# wlpkt1_cpu.net
KiCad netlist of a schematic drawn in Altium Designer
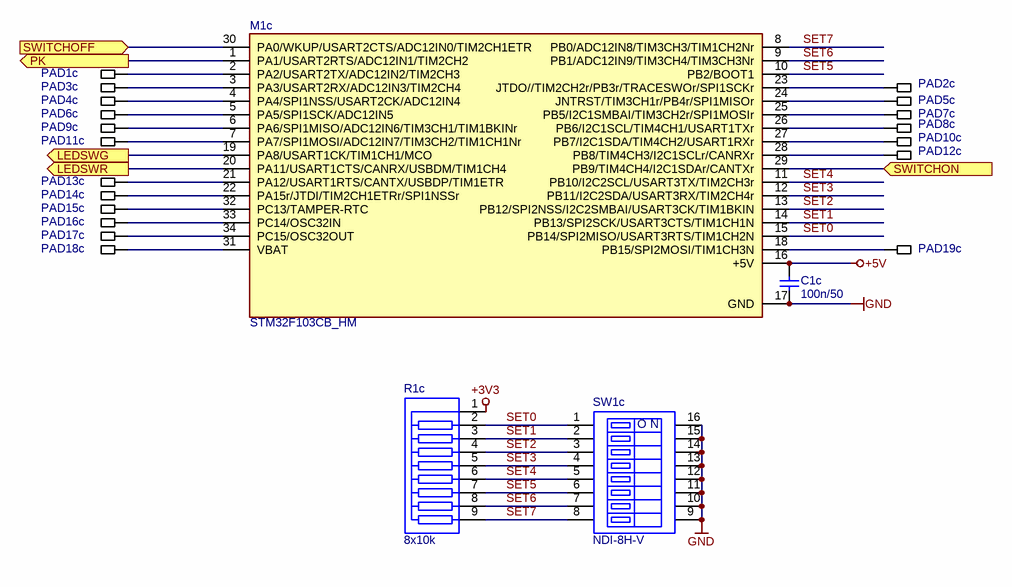
[diagram p0: wlpkt1_cpu.SchDoc]

(export (version "E")
  (design (tool "Eeschema 10.0.6"))
  (components
    (comp (ref "C1c") (value "100n/50") (footprint "0805") (libsource (lib "PartsMySQL") (part "C")))
    (comp (ref "M1c")
      (value "STM32F103CB_HM")
      (footprint "STM32F103CB_HM")
      (libsource (lib "PartsMySQL") (part "STM32F103CB_HM"))
    )
    (comp (ref "PAD1c") (value "PAD0_6MM") (footprint "PAD0_6MM") (libsource (lib "") (part "CLAMP_NOBOM_1")))
    (comp (ref "PAD2c")
      (value "PAD0_6MM")
      (footprint "PAD0_6MM")
      (libsource (lib "PartsMySQL") (part "CLAMP_NOBOM"))
    )
    (comp (ref "PAD3c") (value "PAD0_6MM") (footprint "PAD0_6MM") (libsource (lib "") (part "CLAMP_NOBOM_1")))
    (comp (ref "PAD4c") (value "PAD0_6MM") (footprint "PAD0_6MM") (libsource (lib "") (part "CLAMP_NOBOM_1")))
    (comp (ref "PAD5c")
      (value "PAD0_6MM")
      (footprint "PAD0_6MM")
      (libsource (lib "PartsMySQL") (part "CLAMP_NOBOM"))
    )
    (comp (ref "PAD6c") (value "PAD0_6MM") (footprint "PAD0_6MM") (libsource (lib "") (part "CLAMP_NOBOM_1")))
    (comp (ref "PAD7c")
      (value "PAD0_6MM")
      (footprint "PAD0_6MM")
      (libsource (lib "PartsMySQL") (part "CLAMP_NOBOM"))
    )
    (comp (ref "PAD8c")
      (value "PAD0_6MM")
      (footprint "PAD0_6MM")
      (libsource (lib "PartsMySQL") (part "CLAMP_NOBOM"))
    )
    (comp (ref "PAD9c") (value "PAD0_6MM") (footprint "PAD0_6MM") (libsource (lib "") (part "CLAMP_NOBOM_2")))
    (comp (ref "PAD10c")
      (value "PAD0_6MM")
      (footprint "PAD0_6MM")
      (libsource (lib "PartsMySQL") (part "CLAMP_NOBOM"))
    )
    (comp (ref "PAD11c")
      (value "PAD0_6MM")
      (footprint "PAD0_6MM")
      (libsource (lib "") (part "CLAMP_NOBOM_1"))
    )
    (comp (ref "PAD12c")
      (value "PAD0_6MM")
      (footprint "PAD0_6MM")
      (libsource (lib "PartsMySQL") (part "CLAMP_NOBOM"))
    )
    (comp (ref "PAD13c")
      (value "PAD0_6MM")
      (footprint "PAD0_6MM")
      (libsource (lib "") (part "CLAMP_NOBOM_1"))
    )
    (comp (ref "PAD14c")
      (value "PAD0_6MM")
      (footprint "PAD0_6MM")
      (libsource (lib "") (part "CLAMP_NOBOM_1"))
    )
    (comp (ref "PAD15c")
      (value "PAD0_6MM")
      (footprint "PAD0_6MM")
      (libsource (lib "") (part "CLAMP_NOBOM_1"))
    )
    (comp (ref "PAD16c")
      (value "PAD0_6MM")
      (footprint "PAD0_6MM")
      (libsource (lib "") (part "CLAMP_NOBOM_1"))
    )
    (comp (ref "PAD17c")
      (value "PAD0_6MM")
      (footprint "PAD0_6MM")
      (libsource (lib "") (part "CLAMP_NOBOM_1"))
    )
    (comp (ref "PAD18c")
      (value "PAD0_6MM")
      (footprint "PAD0_6MM")
      (libsource (lib "") (part "CLAMP_NOBOM_1"))
    )
    (comp (ref "PAD19c")
      (value "PAD0_6MM")
      (footprint "PAD0_6MM")
      (libsource (lib "") (part "CLAMP_NOBOM_3"))
    )
    (comp (ref "R1c") (value "8x10k") (footprint "9SIP100") (libsource (lib "PartsMySQL") (part "R-PACK8-C")))
    (comp (ref "SW1c")
      (value "NDI-8H-V")
      (footprint "EAH108E")
      (libsource (lib "PartsMySQL") (part "SWDIP8"))
    )
  )
  (nets
    (net (code "1") (name "+3V3") (class "Default")
      (node (ref "R1c") (pin "1") (pinfunction "1_1") (pintype "passive"))
    )
    (net (code "2") (name "+5V") (class "Default")
      (node (ref "C1c") (pin "1") (pinfunction "1_1") (pintype "passive"))
      (node (ref "M1c") (pin "16") (pinfunction "+5V_16") (pintype "passive"))
    )
    (net (code "3") (name "/LEDSWG") (class "Default")
      (node (ref "M1c") (pin "19") (pinfunction "PA8/USART1CK/TIM1CH1/MCO_19") (pintype "passive"))
    )
    (net (code "4") (name "/LEDSWR") (class "Default")
      (node (ref "M1c") (pin "20") (pinfunction "PA11/USART1CTS/CANRX/USBDM/TIM1CH4_20") (pintype "passive"))
    )
    (net (code "5") (name "/PK") (class "Default")
      (node (ref "M1c") (pin "1") (pinfunction "PA1/USART2RTS/ADC12IN1/TIM2CH2_1") (pintype "passive"))
    )
    (net (code "6") (name "/SET0") (class "Default")
      (node (ref "M1c") (pin "15") (pinfunction "PB14/SPI2MISO/USART3RTS/TIM1CH2N_15") (pintype "passive"))
      (node (ref "R1c") (pin "2") (pinfunction "R8_2") (pintype "passive"))
      (node (ref "SW1c") (pin "1") (pinfunction "1_1") (pintype "passive"))
    )
    (net (code "7") (name "/SET1") (class "Default")
      (node (ref "M1c") (pin "14") (pinfunction "PB13/SPI2SCK/USART3CTS/TIM1CH1N_14") (pintype "passive"))
      (node (ref "R1c") (pin "3") (pinfunction "R7_3") (pintype "passive"))
      (node (ref "SW1c") (pin "2") (pinfunction "2_2") (pintype "passive"))
    )
    (net (code "8") (name "/SET2") (class "Default")
      (node (ref "M1c") (pin "13") (pinfunction "PB12/SPI2NSS/I2C2SMBAI/USART3CK/TIM1BKIN_13") (pintype "passive"))
      (node (ref "R1c") (pin "4") (pinfunction "R6_4") (pintype "passive"))
      (node (ref "SW1c") (pin "3") (pinfunction "3_3") (pintype "passive"))
    )
    (net (code "9") (name "/SET3") (class "Default")
      (node (ref "M1c") (pin "12") (pinfunction "PB11/I2C2SDA/USART3RX/TIM2CH4r_12") (pintype "passive"))
      (node (ref "R1c") (pin "5") (pinfunction "R5_5") (pintype "passive"))
      (node (ref "SW1c") (pin "4") (pinfunction "4_4") (pintype "passive"))
    )
    (net (code "10") (name "/SET4") (class "Default")
      (node (ref "M1c") (pin "11") (pinfunction "PB10/I2C2SCL/USART3TX/TIM2CH3r_11") (pintype "passive"))
      (node (ref "R1c") (pin "6") (pinfunction "R4_6") (pintype "passive"))
      (node (ref "SW1c") (pin "5") (pinfunction "5_5") (pintype "passive"))
    )
    (net (code "11") (name "/SET5") (class "Default")
      (node (ref "M1c") (pin "10") (pinfunction "PB2/BOOT1_10") (pintype "passive"))
      (node (ref "R1c") (pin "7") (pinfunction "R3_7") (pintype "passive"))
      (node (ref "SW1c") (pin "6") (pinfunction "6_6") (pintype "passive"))
    )
    (net (code "12") (name "/SET6") (class "Default")
      (node (ref "M1c") (pin "9") (pinfunction "PB1/ADC12IN9/TIM3CH4/TIM3CH3Nr_9") (pintype "passive"))
      (node (ref "R1c") (pin "8") (pinfunction "R2_8") (pintype "passive"))
      (node (ref "SW1c") (pin "7") (pinfunction "7_7") (pintype "passive"))
    )
    (net (code "13") (name "/SET7") (class "Default")
      (node (ref "M1c") (pin "8") (pinfunction "PB0/ADC12IN8/TIM3CH3/TIM1CH2Nr_8") (pintype "passive"))
      (node (ref "R1c") (pin "9") (pinfunction "R1_9") (pintype "passive"))
      (node (ref "SW1c") (pin "8") (pinfunction "8_8") (pintype "passive"))
    )
    (net (code "14") (name "/SWITCHOFF") (class "Default")
      (node (ref "M1c") (pin "30") (pinfunction "PA0/WKUP/USART2CTS/ADC12IN0/TIM2CH1ETR_30") (pintype "passive"))
    )
    (net (code "15") (name "/SWITCHON") (class "Default")
      (node (ref "M1c") (pin "29") (pinfunction "PB9/TIM4CH4/I2C1SDAr/CANTXr_29") (pintype "passive"))
    )
    (net (code "16") (name "GND") (class "Default")
      (node (ref "C1c") (pin "2") (pinfunction "2_2") (pintype "passive"))
      (node (ref "M1c") (pin "17") (pinfunction "GND_17") (pintype "passive"))
      (node (ref "SW1c") (pin "10") (pinfunction "10_10") (pintype "passive"))
      (node (ref "SW1c") (pin "11") (pinfunction "7_11") (pintype "passive"))
      (node (ref "SW1c") (pin "12") (pinfunction "8_12") (pintype "passive"))
      (node (ref "SW1c") (pin "13") (pinfunction "5_13") (pintype "passive"))
      (node (ref "SW1c") (pin "14") (pinfunction "6_14") (pintype "passive"))
      (node (ref "SW1c") (pin "15") (pinfunction "3_15") (pintype "passive"))
      (node (ref "SW1c") (pin "16") (pinfunction "4_16") (pintype "passive"))
      (node (ref "SW1c") (pin "9") (pinfunction "9_9") (pintype "passive"))
    )
    (net (code "17") (name "Net-(M1c-JNTRST{slash}TIM3CH1r{slash}PB4r{slash}SPI1MISOr)") (class "Default")
      (node (ref "M1c") (pin "24") (pinfunction "JNTRST/TIM3CH1r/PB4r/SPI1MISOr_24") (pintype "passive"))
      (node (ref "PAD5c") (pin "1") (pinfunction "1_1") (pintype "passive"))
    )
    (net (code "18") (name "Net-(M1c-JTDO{slash}{slash}TIM2CH2r{slash}PB3r{slash}TRACESWOr{slash}SPI1SCKr)") (class "Default")
      (node (ref "M1c") (pin "23") (pinfunction "JTDO//TIM2CH2r/PB3r/TRACESWOr/SPI1SCKr_23") (pintype "passive"))
      (node (ref "PAD2c") (pin "1") (pinfunction "1_1") (pintype "passive"))
    )
    (net (code "19") (name "Net-(M1c-PA2{slash}USART2TX{slash}ADC12IN2{slash}TIM2CH3)") (class "Default")
      (node (ref "M1c") (pin "2") (pinfunction "PA2/USART2TX/ADC12IN2/TIM2CH3_2") (pintype "passive"))
      (node (ref "PAD1c") (pin "1") (pinfunction "1_1") (pintype "passive"))
    )
    (net (code "20") (name "Net-(M1c-PA3{slash}USART2RX{slash}ADC12IN3{slash}TIM2CH4)") (class "Default")
      (node (ref "M1c") (pin "3") (pinfunction "PA3/USART2RX/ADC12IN3/TIM2CH4_3") (pintype "passive"))
      (node (ref "PAD3c") (pin "1") (pinfunction "1_1") (pintype "passive"))
    )
    (net (code "21") (name "Net-(M1c-PA4{slash}SPI1NSS{slash}USART2CK{slash}ADC12IN4)") (class "Default")
      (node (ref "M1c") (pin "4") (pinfunction "PA4/SPI1NSS/USART2CK/ADC12IN4_4") (pintype "passive"))
      (node (ref "PAD4c") (pin "1") (pinfunction "1_1") (pintype "passive"))
    )
    (net (code "22") (name "Net-(M1c-PA5{slash}SPI1SCK{slash}ADC12IN5)") (class "Default")
      (node (ref "M1c") (pin "5") (pinfunction "PA5/SPI1SCK/ADC12IN5_5") (pintype "passive"))
      (node (ref "PAD6c") (pin "1") (pinfunction "1_1") (pintype "passive"))
    )
    (net (code "23") (name "Net-(M1c-PA6{slash}SPI1MISO{slash}ADC12IN6{slash}TIM3CH1{slash}TIM1BKINr)") (class "Default")
      (node (ref "M1c") (pin "6") (pinfunction "PA6/SPI1MISO/ADC12IN6/TIM3CH1/TIM1BKINr_6") (pintype "passive"))
      (node (ref "PAD9c") (pin "1") (pinfunction "1_1") (pintype "passive"))
    )
    (net (code "24") (name "Net-(M1c-PA7{slash}SPI1MOSI{slash}ADC12IN7{slash}TIM3CH2{slash}TIM1CH1Nr)") (class "Default")
      (node (ref "M1c") (pin "7") (pinfunction "PA7/SPI1MOSI/ADC12IN7/TIM3CH2/TIM1CH1Nr_7") (pintype "passive"))
      (node (ref "PAD11c") (pin "1") (pinfunction "1_1") (pintype "passive"))
    )
    (net (code "25") (name "Net-(M1c-PA12{slash}USART1RTS{slash}CANTX{slash}USBDP{slash}TIM1ETR)") (class "Default")
      (node (ref "M1c") (pin "21") (pinfunction "PA12/USART1RTS/CANTX/USBDP/TIM1ETR_21") (pintype "passive"))
      (node (ref "PAD13c") (pin "1") (pinfunction "1_1") (pintype "passive"))
    )
    (net (code "26") (name "Net-(M1c-PA15r{slash}JTDI{slash}TIM2CH1ETRr{slash}SPI1NSSr)") (class "Default")
      (node (ref "M1c") (pin "22") (pinfunction "PA15r/JTDI/TIM2CH1ETRr/SPI1NSSr_22") (pintype "passive"))
      (node (ref "PAD14c") (pin "1") (pinfunction "1_1") (pintype "passive"))
    )
    (net (code "27") (name "Net-(M1c-PB5{slash}I2C1SMBAI{slash}TIM3CH2r{slash}SPI1MOSIr)") (class "Default")
      (node (ref "M1c") (pin "25") (pinfunction "PB5/I2C1SMBAI/TIM3CH2r/SPI1MOSIr_25") (pintype "passive"))
      (node (ref "PAD7c") (pin "1") (pinfunction "1_1") (pintype "passive"))
    )
    (net (code "28") (name "Net-(M1c-PB6{slash}I2C1SCL{slash}TIM4CH1{slash}USART1TXr)") (class "Default")
      (node (ref "M1c") (pin "26") (pinfunction "PB6/I2C1SCL/TIM4CH1/USART1TXr_26") (pintype "passive"))
      (node (ref "PAD8c") (pin "1") (pinfunction "1_1") (pintype "passive"))
    )
    (net (code "29") (name "Net-(M1c-PB7{slash}I2C1SDA{slash}TIM4CH2{slash}USART1RXr)") (class "Default")
      (node (ref "M1c") (pin "27") (pinfunction "PB7/I2C1SDA/TIM4CH2/USART1RXr_27") (pintype "passive"))
      (node (ref "PAD10c") (pin "1") (pinfunction "1_1") (pintype "passive"))
    )
    (net (code "30") (name "Net-(M1c-PB8{slash}TIM4CH3{slash}I2C1SCLr{slash}CANRXr)") (class "Default")
      (node (ref "M1c") (pin "28") (pinfunction "PB8/TIM4CH3/I2C1SCLr/CANRXr_28") (pintype "passive"))
      (node (ref "PAD12c") (pin "1") (pinfunction "1_1") (pintype "passive"))
    )
    (net (code "31") (name "Net-(M1c-PB15{slash}SPI2MOSI{slash}TIM1CH3N)") (class "Default")
      (node (ref "M1c") (pin "18") (pinfunction "PB15/SPI2MOSI/TIM1CH3N_18") (pintype "passive"))
      (node (ref "PAD19c") (pin "1") (pinfunction "1_1") (pintype "passive"))
    )
    (net (code "32") (name "Net-(M1c-PC13{slash}TAMPER-RTC)") (class "Default")
      (node (ref "M1c") (pin "32") (pinfunction "PC13/TAMPER-RTC_32") (pintype "passive"))
      (node (ref "PAD15c") (pin "1") (pinfunction "1_1") (pintype "passive"))
    )
    (net (code "33") (name "Net-(M1c-PC14{slash}OSC32IN)") (class "Default")
      (node (ref "M1c") (pin "33") (pinfunction "PC14/OSC32IN_33") (pintype "passive"))
      (node (ref "PAD16c") (pin "1") (pinfunction "1_1") (pintype "passive"))
    )
    (net (code "34") (name "Net-(M1c-PC15{slash}OSC32OUT)") (class "Default")
      (node (ref "M1c") (pin "34") (pinfunction "PC15/OSC32OUT_34") (pintype "passive"))
      (node (ref "PAD17c") (pin "1") (pinfunction "1_1") (pintype "passive"))
    )
    (net (code "35") (name "Net-(M1c-VBAT)") (class "Default")
      (node (ref "M1c") (pin "31") (pinfunction "VBAT_31") (pintype "passive"))
      (node (ref "PAD18c") (pin "1") (pinfunction "1_1") (pintype "passive"))
    )
  )
)
